# LEDARRAY.net
KiCad netlist of a schematic drawn in EAGLE
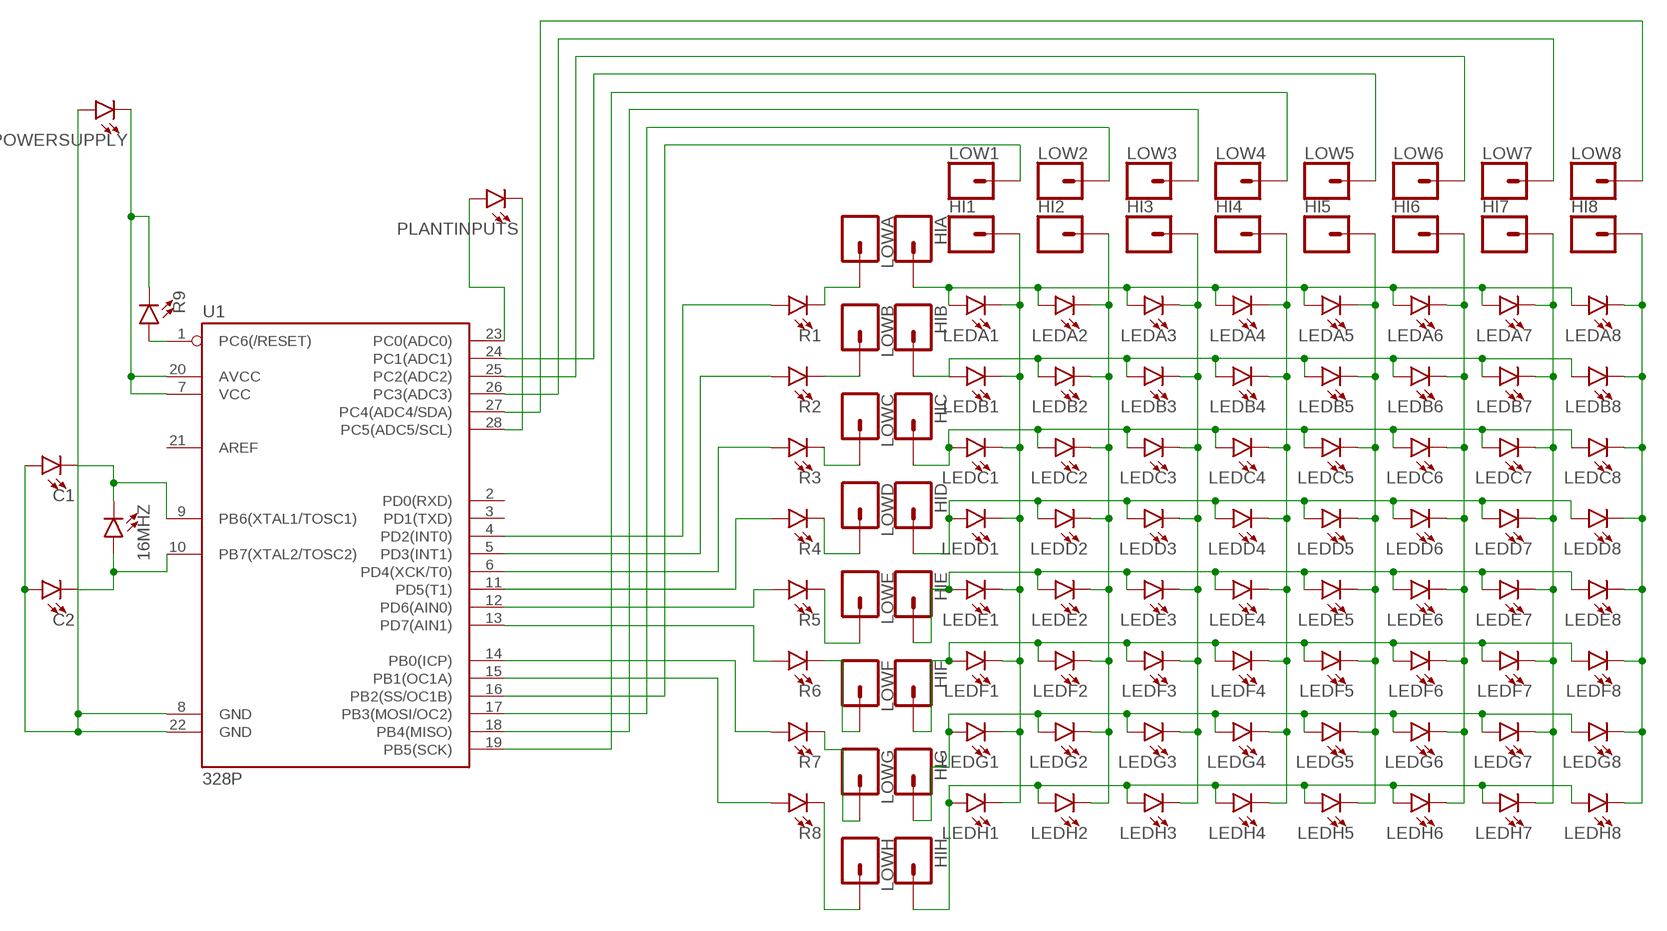
[diagram p0: schematic, sheet 1]

(export (version "E")
  (design (tool "Eeschema 10.0.6"))
  (components
    (comp (ref "16MHZ")
      (value "LED3MM")
      (footprint "eagle-import:LED_3MM")
      (libsource (lib "eagle-import") (part "LED3MM"))
    )
    (comp (ref "C1")
      (value "LED3MM")
      (footprint "eagle-import:LED_3MM")
      (libsource (lib "eagle-import") (part "LED3MM"))
    )
    (comp (ref "C2")
      (value "LED3MM")
      (footprint "eagle-import:LED_3MM")
      (libsource (lib "eagle-import") (part "LED3MM"))
    )
    (comp (ref "HI1")
      (value "CONN_01PTH_NO_SILK_KIT")
      (footprint "eagle-import:1X01NS_KIT")
      (libsource (lib "eagle-import") (part "CONN_01PTH_NO_SILK_KIT"))
    )
    (comp (ref "HI2")
      (value "CONN_01PTH_NO_SILK_KIT")
      (footprint "eagle-import:1X01NS_KIT")
      (libsource (lib "eagle-import") (part "CONN_01PTH_NO_SILK_KIT"))
    )
    (comp (ref "HI3")
      (value "CONN_01PTH_NO_SILK_KIT")
      (footprint "eagle-import:1X01NS_KIT")
      (libsource (lib "eagle-import") (part "CONN_01PTH_NO_SILK_KIT"))
    )
    (comp (ref "HI4")
      (value "CONN_01PTH_NO_SILK_KIT")
      (footprint "eagle-import:1X01NS_KIT")
      (libsource (lib "eagle-import") (part "CONN_01PTH_NO_SILK_KIT"))
    )
    (comp (ref "HI5")
      (value "CONN_01PTH_NO_SILK_KIT")
      (footprint "eagle-import:1X01NS_KIT")
      (libsource (lib "eagle-import") (part "CONN_01PTH_NO_SILK_KIT"))
    )
    (comp (ref "HI6")
      (value "CONN_01PTH_NO_SILK_KIT")
      (footprint "eagle-import:1X01NS_KIT")
      (libsource (lib "eagle-import") (part "CONN_01PTH_NO_SILK_KIT"))
    )
    (comp (ref "HI7")
      (value "CONN_01PTH_NO_SILK_KIT")
      (footprint "eagle-import:1X01NS_KIT")
      (libsource (lib "eagle-import") (part "CONN_01PTH_NO_SILK_KIT"))
    )
    (comp (ref "HI8")
      (value "CONN_01PTH_NO_SILK_KIT")
      (footprint "eagle-import:1X01NS_KIT")
      (libsource (lib "eagle-import") (part "CONN_01PTH_NO_SILK_KIT"))
    )
    (comp (ref "HIA")
      (value "CONN_01PTH_NO_SILK_KIT")
      (footprint "eagle-import:1X01NS_KIT")
      (libsource (lib "eagle-import") (part "CONN_01PTH_NO_SILK_KIT"))
    )
    (comp (ref "HIB")
      (value "CONN_01PTH_NO_SILK_KIT")
      (footprint "eagle-import:1X01NS_KIT")
      (libsource (lib "eagle-import") (part "CONN_01PTH_NO_SILK_KIT"))
    )
    (comp (ref "HIC")
      (value "CONN_01PTH_NO_SILK_KIT")
      (footprint "eagle-import:1X01NS_KIT")
      (libsource (lib "eagle-import") (part "CONN_01PTH_NO_SILK_KIT"))
    )
    (comp (ref "HID")
      (value "CONN_01PTH_NO_SILK_KIT")
      (footprint "eagle-import:1X01NS_KIT")
      (libsource (lib "eagle-import") (part "CONN_01PTH_NO_SILK_KIT"))
    )
    (comp (ref "HIE")
      (value "CONN_01PTH_NO_SILK_KIT")
      (footprint "eagle-import:1X01NS_KIT")
      (libsource (lib "eagle-import") (part "CONN_01PTH_NO_SILK_KIT"))
    )
    (comp (ref "HIF")
      (value "CONN_01PTH_NO_SILK_KIT")
      (footprint "eagle-import:1X01NS_KIT")
      (libsource (lib "eagle-import") (part "CONN_01PTH_NO_SILK_KIT"))
    )
    (comp (ref "HIG")
      (value "CONN_01PTH_NO_SILK_KIT")
      (footprint "eagle-import:1X01NS_KIT")
      (libsource (lib "eagle-import") (part "CONN_01PTH_NO_SILK_KIT"))
    )
    (comp (ref "HIH")
      (value "CONN_01PTH_NO_SILK_KIT")
      (footprint "eagle-import:1X01NS_KIT")
      (libsource (lib "eagle-import") (part "CONN_01PTH_NO_SILK_KIT"))
    )
    (comp (ref "LEDA1")
      (value "LED3MM")
      (footprint "eagle-import:LED_3MM")
      (libsource (lib "eagle-import") (part "LED3MM"))
    )
    (comp (ref "LEDA2")
      (value "LED3MM")
      (footprint "eagle-import:LED_3MM")
      (libsource (lib "eagle-import") (part "LED3MM"))
    )
    (comp (ref "LEDA3")
      (value "LED3MM")
      (footprint "eagle-import:LED_3MM")
      (libsource (lib "eagle-import") (part "LED3MM"))
    )
    (comp (ref "LEDA4")
      (value "LED3MM")
      (footprint "eagle-import:LED_3MM")
      (libsource (lib "eagle-import") (part "LED3MM"))
    )
    (comp (ref "LEDA5")
      (value "LED3MM")
      (footprint "eagle-import:LED_3MM")
      (libsource (lib "eagle-import") (part "LED3MM"))
    )
    (comp (ref "LEDA6")
      (value "LED3MM")
      (footprint "eagle-import:LED_3MM")
      (libsource (lib "eagle-import") (part "LED3MM"))
    )
    (comp (ref "LEDA7")
      (value "LED3MM")
      (footprint "eagle-import:LED_3MM")
      (libsource (lib "eagle-import") (part "LED3MM"))
    )
    (comp (ref "LEDA8")
      (value "LED3MM")
      (footprint "eagle-import:LED_3MM")
      (libsource (lib "eagle-import") (part "LED3MM"))
    )
    (comp (ref "LEDB1")
      (value "LED3MM")
      (footprint "eagle-import:LED_3MM")
      (libsource (lib "eagle-import") (part "LED3MM"))
    )
    (comp (ref "LEDB2")
      (value "LED3MM")
      (footprint "eagle-import:LED_3MM")
      (libsource (lib "eagle-import") (part "LED3MM"))
    )
    (comp (ref "LEDB3")
      (value "LED3MM")
      (footprint "eagle-import:LED_3MM")
      (libsource (lib "eagle-import") (part "LED3MM"))
    )
    (comp (ref "LEDB4")
      (value "LED3MM")
      (footprint "eagle-import:LED_3MM")
      (libsource (lib "eagle-import") (part "LED3MM"))
    )
    (comp (ref "LEDB5")
      (value "LED3MM")
      (footprint "eagle-import:LED_3MM")
      (libsource (lib "eagle-import") (part "LED3MM"))
    )
    (comp (ref "LEDB6")
      (value "LED3MM")
      (footprint "eagle-import:LED_3MM")
      (libsource (lib "eagle-import") (part "LED3MM"))
    )
    (comp (ref "LEDB7")
      (value "LED3MM")
      (footprint "eagle-import:LED_3MM")
      (libsource (lib "eagle-import") (part "LED3MM"))
    )
    (comp (ref "LEDB8")
      (value "LED3MM")
      (footprint "eagle-import:LED_3MM")
      (libsource (lib "eagle-import") (part "LED3MM"))
    )
    (comp (ref "LEDC1")
      (value "LED3MM")
      (footprint "eagle-import:LED_3MM")
      (libsource (lib "eagle-import") (part "LED3MM"))
    )
    (comp (ref "LEDC2")
      (value "LED3MM")
      (footprint "eagle-import:LED_3MM")
      (libsource (lib "eagle-import") (part "LED3MM"))
    )
    (comp (ref "LEDC3")
      (value "LED3MM")
      (footprint "eagle-import:LED_3MM")
      (libsource (lib "eagle-import") (part "LED3MM"))
    )
    (comp (ref "LEDC4")
      (value "LED3MM")
      (footprint "eagle-import:LED_3MM")
      (libsource (lib "eagle-import") (part "LED3MM"))
    )
    (comp (ref "LEDC5")
      (value "LED3MM")
      (footprint "eagle-import:LED_3MM")
      (libsource (lib "eagle-import") (part "LED3MM"))
    )
    (comp (ref "LEDC6")
      (value "LED3MM")
      (footprint "eagle-import:LED_3MM")
      (libsource (lib "eagle-import") (part "LED3MM"))
    )
    (comp (ref "LEDC7")
      (value "LED3MM")
      (footprint "eagle-import:LED_3MM")
      (libsource (lib "eagle-import") (part "LED3MM"))
    )
    (comp (ref "LEDC8")
      (value "LED3MM")
      (footprint "eagle-import:LED_3MM")
      (libsource (lib "eagle-import") (part "LED3MM"))
    )
    (comp (ref "LEDD1")
      (value "LED3MM")
      (footprint "eagle-import:LED_3MM")
      (libsource (lib "eagle-import") (part "LED3MM"))
    )
    (comp (ref "LEDD2")
      (value "LED3MM")
      (footprint "eagle-import:LED_3MM")
      (libsource (lib "eagle-import") (part "LED3MM"))
    )
    (comp (ref "LEDD3")
      (value "LED3MM")
      (footprint "eagle-import:LED_3MM")
      (libsource (lib "eagle-import") (part "LED3MM"))
    )
    (comp (ref "LEDD4")
      (value "LED3MM")
      (footprint "eagle-import:LED_3MM")
      (libsource (lib "eagle-import") (part "LED3MM"))
    )
    (comp (ref "LEDD5")
      (value "LED3MM")
      (footprint "eagle-import:LED_3MM")
      (libsource (lib "eagle-import") (part "LED3MM"))
    )
    (comp (ref "LEDD6")
      (value "LED3MM")
      (footprint "eagle-import:LED_3MM")
      (libsource (lib "eagle-import") (part "LED3MM"))
    )
    (comp (ref "LEDD7")
      (value "LED3MM")
      (footprint "eagle-import:LED_3MM")
      (libsource (lib "eagle-import") (part "LED3MM"))
    )
    (comp (ref "LEDD8")
      (value "LED3MM")
      (footprint "eagle-import:LED_3MM")
      (libsource (lib "eagle-import") (part "LED3MM"))
    )
    (comp (ref "LEDE1")
      (value "LED3MM")
      (footprint "eagle-import:LED_3MM")
      (libsource (lib "eagle-import") (part "LED3MM"))
    )
    (comp (ref "LEDE2")
      (value "LED3MM")
      (footprint "eagle-import:LED_3MM")
      (libsource (lib "eagle-import") (part "LED3MM"))
    )
    (comp (ref "LEDE3")
      (value "LED3MM")
      (footprint "eagle-import:LED_3MM")
      (libsource (lib "eagle-import") (part "LED3MM"))
    )
    (comp (ref "LEDE4")
      (value "LED3MM")
      (footprint "eagle-import:LED_3MM")
      (libsource (lib "eagle-import") (part "LED3MM"))
    )
    (comp (ref "LEDE5")
      (value "LED3MM")
      (footprint "eagle-import:LED_3MM")
      (libsource (lib "eagle-import") (part "LED3MM"))
    )
    (comp (ref "LEDE6")
      (value "LED3MM")
      (footprint "eagle-import:LED_3MM")
      (libsource (lib "eagle-import") (part "LED3MM"))
    )
    (comp (ref "LEDE7")
      (value "LED3MM")
      (footprint "eagle-import:LED_3MM")
      (libsource (lib "eagle-import") (part "LED3MM"))
    )
    (comp (ref "LEDE8")
      (value "LED3MM")
      (footprint "eagle-import:LED_3MM")
      (libsource (lib "eagle-import") (part "LED3MM"))
    )
    (comp (ref "LEDF1")
      (value "LED3MM")
      (footprint "eagle-import:LED_3MM")
      (libsource (lib "eagle-import") (part "LED3MM"))
    )
    (comp (ref "LEDF2")
      (value "LED3MM")
      (footprint "eagle-import:LED_3MM")
      (libsource (lib "eagle-import") (part "LED3MM"))
    )
    (comp (ref "LEDF3")
      (value "LED3MM")
      (footprint "eagle-import:LED_3MM")
      (libsource (lib "eagle-import") (part "LED3MM"))
    )
    (comp (ref "LEDF4")
      (value "LED3MM")
      (footprint "eagle-import:LED_3MM")
      (libsource (lib "eagle-import") (part "LED3MM"))
    )
    (comp (ref "LEDF5")
      (value "LED3MM")
      (footprint "eagle-import:LED_3MM")
      (libsource (lib "eagle-import") (part "LED3MM"))
    )
    (comp (ref "LEDF6")
      (value "LED3MM")
      (footprint "eagle-import:LED_3MM")
      (libsource (lib "eagle-import") (part "LED3MM"))
    )
    (comp (ref "LEDF7")
      (value "LED3MM")
      (footprint "eagle-import:LED_3MM")
      (libsource (lib "eagle-import") (part "LED3MM"))
    )
    (comp (ref "LEDF8")
      (value "LED3MM")
      (footprint "eagle-import:LED_3MM")
      (libsource (lib "eagle-import") (part "LED3MM"))
    )
    (comp (ref "LEDG1")
      (value "LED3MM")
      (footprint "eagle-import:LED_3MM")
      (libsource (lib "eagle-import") (part "LED3MM"))
    )
    (comp (ref "LEDG2")
      (value "LED3MM")
      (footprint "eagle-import:LED_3MM")
      (libsource (lib "eagle-import") (part "LED3MM"))
    )
    (comp (ref "LEDG3")
      (value "LED3MM")
      (footprint "eagle-import:LED_3MM")
      (libsource (lib "eagle-import") (part "LED3MM"))
    )
    (comp (ref "LEDG4")
      (value "LED3MM")
      (footprint "eagle-import:LED_3MM")
      (libsource (lib "eagle-import") (part "LED3MM"))
    )
    (comp (ref "LEDG5")
      (value "LED3MM")
      (footprint "eagle-import:LED_3MM")
      (libsource (lib "eagle-import") (part "LED3MM"))
    )
    (comp (ref "LEDG6")
      (value "LED3MM")
      (footprint "eagle-import:LED_3MM")
      (libsource (lib "eagle-import") (part "LED3MM"))
    )
    (comp (ref "LEDG7")
      (value "LED3MM")
      (footprint "eagle-import:LED_3MM")
      (libsource (lib "eagle-import") (part "LED3MM"))
    )
    (comp (ref "LEDG8")
      (value "LED3MM")
      (footprint "eagle-import:LED_3MM")
      (libsource (lib "eagle-import") (part "LED3MM"))
    )
    (comp (ref "LEDH1")
      (value "LED3MM")
      (footprint "eagle-import:LED_3MM")
      (libsource (lib "eagle-import") (part "LED3MM"))
    )
    (comp (ref "LEDH2")
      (value "LED3MM")
      (footprint "eagle-import:LED_3MM")
      (libsource (lib "eagle-import") (part "LED3MM"))
    )
    (comp (ref "LEDH3")
      (value "LED3MM")
      (footprint "eagle-import:LED_3MM")
      (libsource (lib "eagle-import") (part "LED3MM"))
    )
    (comp (ref "LEDH4")
      (value "LED3MM")
      (footprint "eagle-import:LED_3MM")
      (libsource (lib "eagle-import") (part "LED3MM"))
    )
    (comp (ref "LEDH5")
      (value "LED3MM")
      (footprint "eagle-import:LED_3MM")
      (libsource (lib "eagle-import") (part "LED3MM"))
    )
    (comp (ref "LEDH6")
      (value "LED3MM")
      (footprint "eagle-import:LED_3MM")
      (libsource (lib "eagle-import") (part "LED3MM"))
    )
    (comp (ref "LEDH7")
      (value "LED3MM")
      (footprint "eagle-import:LED_3MM")
      (libsource (lib "eagle-import") (part "LED3MM"))
    )
    (comp (ref "LEDH8")
      (value "LED3MM")
      (footprint "eagle-import:LED_3MM")
      (libsource (lib "eagle-import") (part "LED3MM"))
    )
    (comp (ref "LOW1")
      (value "CONN_01PTH_NO_SILK_KIT")
      (footprint "eagle-import:1X01NS_KIT")
      (libsource (lib "eagle-import") (part "CONN_01PTH_NO_SILK_KIT"))
    )
    (comp (ref "LOW2")
      (value "CONN_01PTH_NO_SILK_KIT")
      (footprint "eagle-import:1X01NS_KIT")
      (libsource (lib "eagle-import") (part "CONN_01PTH_NO_SILK_KIT"))
    )
    (comp (ref "LOW3")
      (value "CONN_01PTH_NO_SILK_KIT")
      (footprint "eagle-import:1X01NS_KIT")
      (libsource (lib "eagle-import") (part "CONN_01PTH_NO_SILK_KIT"))
    )
    (comp (ref "LOW4")
      (value "CONN_01PTH_NO_SILK_KIT")
      (footprint "eagle-import:1X01NS_KIT")
      (libsource (lib "eagle-import") (part "CONN_01PTH_NO_SILK_KIT"))
    )
    (comp (ref "LOW5")
      (value "CONN_01PTH_NO_SILK_KIT")
      (footprint "eagle-import:1X01NS_KIT")
      (libsource (lib "eagle-import") (part "CONN_01PTH_NO_SILK_KIT"))
    )
    (comp (ref "LOW6")
      (value "CONN_01PTH_NO_SILK_KIT")
      (footprint "eagle-import:1X01NS_KIT")
      (libsource (lib "eagle-import") (part "CONN_01PTH_NO_SILK_KIT"))
    )
    (comp (ref "LOW7")
      (value "CONN_01PTH_NO_SILK_KIT")
      (footprint "eagle-import:1X01NS_KIT")
      (libsource (lib "eagle-import") (part "CONN_01PTH_NO_SILK_KIT"))
    )
    (comp (ref "LOW8")
      (value "CONN_01PTH_NO_SILK_KIT")
      (footprint "eagle-import:1X01NS_KIT")
      (libsource (lib "eagle-import") (part "CONN_01PTH_NO_SILK_KIT"))
    )
    (comp (ref "LOWA")
      (value "CONN_01PTH_NO_SILK_KIT")
      (footprint "eagle-import:1X01NS_KIT")
      (libsource (lib "eagle-import") (part "CONN_01PTH_NO_SILK_KIT"))
    )
    (comp (ref "LOWB")
      (value "CONN_01PTH_NO_SILK_KIT")
      (footprint "eagle-import:1X01NS_KIT")
      (libsource (lib "eagle-import") (part "CONN_01PTH_NO_SILK_KIT"))
    )
    (comp (ref "LOWC")
      (value "CONN_01PTH_NO_SILK_KIT")
      (footprint "eagle-import:1X01NS_KIT")
      (libsource (lib "eagle-import") (part "CONN_01PTH_NO_SILK_KIT"))
    )
    (comp (ref "LOWD")
      (value "CONN_01PTH_NO_SILK_KIT")
      (footprint "eagle-import:1X01NS_KIT")
      (libsource (lib "eagle-import") (part "CONN_01PTH_NO_SILK_KIT"))
    )
    (comp (ref "LOWE")
      (value "CONN_01PTH_NO_SILK_KIT")
      (footprint "eagle-import:1X01NS_KIT")
      (libsource (lib "eagle-import") (part "CONN_01PTH_NO_SILK_KIT"))
    )
    (comp (ref "LOWF")
      (value "CONN_01PTH_NO_SILK_KIT")
      (footprint "eagle-import:1X01NS_KIT")
      (libsource (lib "eagle-import") (part "CONN_01PTH_NO_SILK_KIT"))
    )
    (comp (ref "LOWG")
      (value "CONN_01PTH_NO_SILK_KIT")
      (footprint "eagle-import:1X01NS_KIT")
      (libsource (lib "eagle-import") (part "CONN_01PTH_NO_SILK_KIT"))
    )
    (comp (ref "LOWH")
      (value "CONN_01PTH_NO_SILK_KIT")
      (footprint "eagle-import:1X01NS_KIT")
      (libsource (lib "eagle-import") (part "CONN_01PTH_NO_SILK_KIT"))
    )
    (comp (ref "PLANTINPUTS")
      (value "LED3MM")
      (footprint "eagle-import:LED_3MM")
      (libsource (lib "eagle-import") (part "LED3MM"))
    )
    (comp (ref "POWERSUPPLY")
      (value "LED3MM")
      (footprint "eagle-import:LED_3MM")
      (libsource (lib "eagle-import") (part "LED3MM"))
    )
    (comp (ref "R1")
      (value "LED3MM")
      (footprint "eagle-import:LED_3MM")
      (libsource (lib "eagle-import") (part "LED3MM"))
    )
    (comp (ref "R2")
      (value "LED3MM")
      (footprint "eagle-import:LED_3MM")
      (libsource (lib "eagle-import") (part "LED3MM"))
    )
    (comp (ref "R3")
      (value "LED3MM")
      (footprint "eagle-import:LED_3MM")
      (libsource (lib "eagle-import") (part "LED3MM"))
    )
    (comp (ref "R4")
      (value "LED3MM")
      (footprint "eagle-import:LED_3MM")
      (libsource (lib "eagle-import") (part "LED3MM"))
    )
    (comp (ref "R5")
      (value "LED3MM")
      (footprint "eagle-import:LED_3MM")
      (libsource (lib "eagle-import") (part "LED3MM"))
    )
    (comp (ref "R6")
      (value "LED3MM")
      (footprint "eagle-import:LED_3MM")
      (libsource (lib "eagle-import") (part "LED3MM"))
    )
    (comp (ref "R7")
      (value "LED3MM")
      (footprint "eagle-import:LED_3MM")
      (libsource (lib "eagle-import") (part "LED3MM"))
    )
    (comp (ref "R8")
      (value "LED3MM")
      (footprint "eagle-import:LED_3MM")
      (libsource (lib "eagle-import") (part "LED3MM"))
    )
    (comp (ref "R9")
      (value "LED3MM")
      (footprint "eagle-import:LED_3MM")
      (libsource (lib "eagle-import") (part "LED3MM"))
    )
    (comp (ref "U1")
      (value "328P")
      (footprint "eagle-import:DIP28")
      (libsource (lib "eagle-import") (part "ATMEGA328P_PDIP"))
    )
  )
  (nets
    (net (code "1") (name "Net-(16MHZ-C)") (class "Default")
      (node (ref "16MHZ") (pin "K") (pinfunction "C_K") (pintype "passive"))
      (node (ref "C1") (pin "K") (pinfunction "C_K") (pintype "passive"))
      (node (ref "U1") (pin "9") (pinfunction "PB6(XTAL1/TOSC1)_9") (pintype "bidirectional"))
    )
    (net (code "2") (name "Net-(C1-PadA)") (class "Default")
      (node (ref "C1") (pin "A") (pinfunction "A_A") (pintype "passive"))
      (node (ref "C2") (pin "A") (pinfunction "A_A") (pintype "passive"))
      (node (ref "POWERSUPPLY") (pin "A") (pinfunction "A_A") (pintype "passive"))
      (node (ref "U1") (pin "22") (pinfunction "GND_22") (pintype "bidirectional"))
      (node (ref "U1") (pin "8") (pinfunction "GND_8") (pintype "bidirectional"))
    )
    (net (code "3") (name "Net-(C2-C)") (class "Default")
      (node (ref "16MHZ") (pin "A") (pinfunction "A_A") (pintype "passive"))
      (node (ref "C2") (pin "K") (pinfunction "C_K") (pintype "passive"))
      (node (ref "U1") (pin "10") (pinfunction "PB7(XTAL2/TOSC2)_10") (pintype "bidirectional"))
    )
    (net (code "4") (name "Net-(HIA-Pad1)") (class "Default")
      (node (ref "HIA") (pin "1") (pinfunction "1_1") (pintype "passive"))
      (node (ref "LEDA1") (pin "A") (pinfunction "A_A") (pintype "passive"))
      (node (ref "LEDA2") (pin "A") (pinfunction "A_A") (pintype "passive"))
      (node (ref "LEDA3") (pin "A") (pinfunction "A_A") (pintype "passive"))
      (node (ref "LEDA4") (pin "A") (pinfunction "A_A") (pintype "passive"))
      (node (ref "LEDA5") (pin "A") (pinfunction "A_A") (pintype "passive"))
      (node (ref "LEDA6") (pin "A") (pinfunction "A_A") (pintype "passive"))
      (node (ref "LEDA7") (pin "A") (pinfunction "A_A") (pintype "passive"))
      (node (ref "LEDA8") (pin "A") (pinfunction "A_A") (pintype "passive"))
    )
    (net (code "5") (name "Net-(HIB-Pad1)") (class "Default")
      (node (ref "HIB") (pin "1") (pinfunction "1_1") (pintype "passive"))
      (node (ref "LEDB1") (pin "A") (pinfunction "A_A") (pintype "passive"))
      (node (ref "LEDB2") (pin "A") (pinfunction "A_A") (pintype "passive"))
      (node (ref "LEDB3") (pin "A") (pinfunction "A_A") (pintype "passive"))
      (node (ref "LEDB4") (pin "A") (pinfunction "A_A") (pintype "passive"))
      (node (ref "LEDB5") (pin "A") (pinfunction "A_A") (pintype "passive"))
      (node (ref "LEDB6") (pin "A") (pinfunction "A_A") (pintype "passive"))
      (node (ref "LEDB7") (pin "A") (pinfunction "A_A") (pintype "passive"))
      (node (ref "LEDB8") (pin "A") (pinfunction "A_A") (pintype "passive"))
    )
    (net (code "6") (name "Net-(HIC-Pad1)") (class "Default")
      (node (ref "HIC") (pin "1") (pinfunction "1_1") (pintype "passive"))
      (node (ref "LEDC1") (pin "A") (pinfunction "A_A") (pintype "passive"))
      (node (ref "LEDC2") (pin "A") (pinfunction "A_A") (pintype "passive"))
      (node (ref "LEDC3") (pin "A") (pinfunction "A_A") (pintype "passive"))
      (node (ref "LEDC4") (pin "A") (pinfunction "A_A") (pintype "passive"))
      (node (ref "LEDC5") (pin "A") (pinfunction "A_A") (pintype "passive"))
      (node (ref "LEDC6") (pin "A") (pinfunction "A_A") (pintype "passive"))
      (node (ref "LEDC7") (pin "A") (pinfunction "A_A") (pintype "passive"))
      (node (ref "LEDC8") (pin "A") (pinfunction "A_A") (pintype "passive"))
    )
    (net (code "7") (name "Net-(HID-Pad1)") (class "Default")
      (node (ref "HID") (pin "1") (pinfunction "1_1") (pintype "passive"))
      (node (ref "LEDD1") (pin "A") (pinfunction "A_A") (pintype "passive"))
      (node (ref "LEDD2") (pin "A") (pinfunction "A_A") (pintype "passive"))
      (node (ref "LEDD3") (pin "A") (pinfunction "A_A") (pintype "passive"))
      (node (ref "LEDD4") (pin "A") (pinfunction "A_A") (pintype "passive"))
      (node (ref "LEDD5") (pin "A") (pinfunction "A_A") (pintype "passive"))
      (node (ref "LEDD6") (pin "A") (pinfunction "A_A") (pintype "passive"))
      (node (ref "LEDD7") (pin "A") (pinfunction "A_A") (pintype "passive"))
      (node (ref "LEDD8") (pin "A") (pinfunction "A_A") (pintype "passive"))
    )
    (net (code "8") (name "Net-(HIE-Pad1)") (class "Default")
      (node (ref "HIE") (pin "1") (pinfunction "1_1") (pintype "passive"))
      (node (ref "LEDE1") (pin "A") (pinfunction "A_A") (pintype "passive"))
      (node (ref "LEDE2") (pin "A") (pinfunction "A_A") (pintype "passive"))
      (node (ref "LEDE3") (pin "A") (pinfunction "A_A") (pintype "passive"))
      (node (ref "LEDE4") (pin "A") (pinfunction "A_A") (pintype "passive"))
      (node (ref "LEDE5") (pin "A") (pinfunction "A_A") (pintype "passive"))
      (node (ref "LEDE6") (pin "A") (pinfunction "A_A") (pintype "passive"))
      (node (ref "LEDE7") (pin "A") (pinfunction "A_A") (pintype "passive"))
      (node (ref "LEDE8") (pin "A") (pinfunction "A_A") (pintype "passive"))
    )
    (net (code "9") (name "Net-(HIF-Pad1)") (class "Default")
      (node (ref "HIF") (pin "1") (pinfunction "1_1") (pintype "passive"))
      (node (ref "LEDF1") (pin "A") (pinfunction "A_A") (pintype "passive"))
      (node (ref "LEDF2") (pin "A") (pinfunction "A_A") (pintype "passive"))
      (node (ref "LEDF3") (pin "A") (pinfunction "A_A") (pintype "passive"))
      (node (ref "LEDF4") (pin "A") (pinfunction "A_A") (pintype "passive"))
      (node (ref "LEDF5") (pin "A") (pinfunction "A_A") (pintype "passive"))
      (node (ref "LEDF6") (pin "A") (pinfunction "A_A") (pintype "passive"))
      (node (ref "LEDF7") (pin "A") (pinfunction "A_A") (pintype "passive"))
      (node (ref "LEDF8") (pin "A") (pinfunction "A_A") (pintype "passive"))
    )
    (net (code "10") (name "Net-(HIG-Pad1)") (class "Default")
      (node (ref "HIG") (pin "1") (pinfunction "1_1") (pintype "passive"))
      (node (ref "LEDG1") (pin "A") (pinfunction "A_A") (pintype "passive"))
      (node (ref "LEDG2") (pin "A") (pinfunction "A_A") (pintype "passive"))
      (node (ref "LEDG3") (pin "A") (pinfunction "A_A") (pintype "passive"))
      (node (ref "LEDG4") (pin "A") (pinfunction "A_A") (pintype "passive"))
      (node (ref "LEDG5") (pin "A") (pinfunction "A_A") (pintype "passive"))
      (node (ref "LEDG6") (pin "A") (pinfunction "A_A") (pintype "passive"))
      (node (ref "LEDG7") (pin "A") (pinfunction "A_A") (pintype "passive"))
      (node (ref "LEDG8") (pin "A") (pinfunction "A_A") (pintype "passive"))
    )
    (net (code "11") (name "Net-(HIH-Pad1)") (class "Default")
      (node (ref "HIH") (pin "1") (pinfunction "1_1") (pintype "passive"))
      (node (ref "LEDH1") (pin "A") (pinfunction "A_A") (pintype "passive"))
      (node (ref "LEDH2") (pin "A") (pinfunction "A_A") (pintype "passive"))
      (node (ref "LEDH3") (pin "A") (pinfunction "A_A") (pintype "passive"))
      (node (ref "LEDH4") (pin "A") (pinfunction "A_A") (pintype "passive"))
      (node (ref "LEDH5") (pin "A") (pinfunction "A_A") (pintype "passive"))
      (node (ref "LEDH6") (pin "A") (pinfunction "A_A") (pintype "passive"))
      (node (ref "LEDH7") (pin "A") (pinfunction "A_A") (pintype "passive"))
      (node (ref "LEDH8") (pin "A") (pinfunction "A_A") (pintype "passive"))
    )
    (net (code "12") (name "Net-(LEDA1-C)") (class "Default")
      (node (ref "HI1") (pin "1") (pinfunction "1_1") (pintype "passive"))
      (node (ref "LEDA1") (pin "K") (pinfunction "C_K") (pintype "passive"))
      (node (ref "LEDB1") (pin "K") (pinfunction "C_K") (pintype "passive"))
      (node (ref "LEDC1") (pin "K") (pinfunction "C_K") (pintype "passive"))
      (node (ref "LEDD1") (pin "K") (pinfunction "C_K") (pintype "passive"))
      (node (ref "LEDE1") (pin "K") (pinfunction "C_K") (pintype "passive"))
      (node (ref "LEDF1") (pin "K") (pinfunction "C_K") (pintype "passive"))
      (node (ref "LEDG1") (pin "K") (pinfunction "C_K") (pintype "passive"))
      (node (ref "LEDH1") (pin "K") (pinfunction "C_K") (pintype "passive"))
    )
    (net (code "13") (name "Net-(LEDA2-C)") (class "Default")
      (node (ref "HI2") (pin "1") (pinfunction "1_1") (pintype "passive"))
      (node (ref "LEDA2") (pin "K") (pinfunction "C_K") (pintype "passive"))
      (node (ref "LEDB2") (pin "K") (pinfunction "C_K") (pintype "passive"))
      (node (ref "LEDC2") (pin "K") (pinfunction "C_K") (pintype "passive"))
      (node (ref "LEDD2") (pin "K") (pinfunction "C_K") (pintype "passive"))
      (node (ref "LEDE2") (pin "K") (pinfunction "C_K") (pintype "passive"))
      (node (ref "LEDF2") (pin "K") (pinfunction "C_K") (pintype "passive"))
      (node (ref "LEDG2") (pin "K") (pinfunction "C_K") (pintype "passive"))
      (node (ref "LEDH2") (pin "K") (pinfunction "C_K") (pintype "passive"))
    )
    (net (code "14") (name "Net-(LEDA3-C)") (class "Default")
      (node (ref "HI3") (pin "1") (pinfunction "1_1") (pintype "passive"))
      (node (ref "LEDA3") (pin "K") (pinfunction "C_K") (pintype "passive"))
      (node (ref "LEDB3") (pin "K") (pinfunction "C_K") (pintype "passive"))
      (node (ref "LEDC3") (pin "K") (pinfunction "C_K") (pintype "passive"))
      (node (ref "LEDD3") (pin "K") (pinfunction "C_K") (pintype "passive"))
      (node (ref "LEDE3") (pin "K") (pinfunction "C_K") (pintype "passive"))
      (node (ref "LEDF3") (pin "K") (pinfunction "C_K") (pintype "passive"))
      (node (ref "LEDG3") (pin "K") (pinfunction "C_K") (pintype "passive"))
      (node (ref "LEDH3") (pin "K") (pinfunction "C_K") (pintype "passive"))
    )
    (net (code "15") (name "Net-(LEDA4-C)") (class "Default")
      (node (ref "HI4") (pin "1") (pinfunction "1_1") (pintype "passive"))
      (node (ref "LEDA4") (pin "K") (pinfunction "C_K") (pintype "passive"))
      (node (ref "LEDB4") (pin "K") (pinfunction "C_K") (pintype "passive"))
      (node (ref "LEDC4") (pin "K") (pinfunction "C_K") (pintype "passive"))
      (node (ref "LEDD4") (pin "K") (pinfunction "C_K") (pintype "passive"))
      (node (ref "LEDE4") (pin "K") (pinfunction "C_K") (pintype "passive"))
      (node (ref "LEDF4") (pin "K") (pinfunction "C_K") (pintype "passive"))
      (node (ref "LEDG4") (pin "K") (pinfunction "C_K") (pintype "passive"))
      (node (ref "LEDH4") (pin "K") (pinfunction "C_K") (pintype "passive"))
    )
    (net (code "16") (name "Net-(LEDA5-C)") (class "Default")
      (node (ref "HI5") (pin "1") (pinfunction "1_1") (pintype "passive"))
      (node (ref "LEDA5") (pin "K") (pinfunction "C_K") (pintype "passive"))
      (node (ref "LEDB5") (pin "K") (pinfunction "C_K") (pintype "passive"))
      (node (ref "LEDC5") (pin "K") (pinfunction "C_K") (pintype "passive"))
      (node (ref "LEDD5") (pin "K") (pinfunction "C_K") (pintype "passive"))
      (node (ref "LEDE5") (pin "K") (pinfunction "C_K") (pintype "passive"))
      (node (ref "LEDF5") (pin "K") (pinfunction "C_K") (pintype "passive"))
      (node (ref "LEDG5") (pin "K") (pinfunction "C_K") (pintype "passive"))
      (node (ref "LEDH5") (pin "K") (pinfunction "C_K") (pintype "passive"))
    )
    (net (code "17") (name "Net-(LEDA6-C)") (class "Default")
      (node (ref "HI6") (pin "1") (pinfunction "1_1") (pintype "passive"))
      (node (ref "LEDA6") (pin "K") (pinfunction "C_K") (pintype "passive"))
      (node (ref "LEDB6") (pin "K") (pinfunction "C_K") (pintype "passive"))
      (node (ref "LEDC6") (pin "K") (pinfunction "C_K") (pintype "passive"))
      (node (ref "LEDD6") (pin "K") (pinfunction "C_K") (pintype "passive"))
      (node (ref "LEDE6") (pin "K") (pinfunction "C_K") (pintype "passive"))
      (node (ref "LEDF6") (pin "K") (pinfunction "C_K") (pintype "passive"))
      (node (ref "LEDG6") (pin "K") (pinfunction "C_K") (pintype "passive"))
      (node (ref "LEDH6") (pin "K") (pinfunction "C_K") (pintype "passive"))
    )
    (net (code "18") (name "Net-(LEDA7-C)") (class "Default")
      (node (ref "HI7") (pin "1") (pinfunction "1_1") (pintype "passive"))
      (node (ref "LEDA7") (pin "K") (pinfunction "C_K") (pintype "passive"))
      (node (ref "LEDB7") (pin "K") (pinfunction "C_K") (pintype "passive"))
      (node (ref "LEDC7") (pin "K") (pinfunction "C_K") (pintype "passive"))
      (node (ref "LEDD7") (pin "K") (pinfunction "C_K") (pintype "passive"))
      (node (ref "LEDE7") (pin "K") (pinfunction "C_K") (pintype "passive"))
      (node (ref "LEDF7") (pin "K") (pinfunction "C_K") (pintype "passive"))
      (node (ref "LEDG7") (pin "K") (pinfunction "C_K") (pintype "passive"))
      (node (ref "LEDH7") (pin "K") (pinfunction "C_K") (pintype "passive"))
    )
    (net (code "19") (name "Net-(LEDA8-C)") (class "Default")
      (node (ref "HI8") (pin "1") (pinfunction "1_1") (pintype "passive"))
      (node (ref "LEDA8") (pin "K") (pinfunction "C_K") (pintype "passive"))
      (node (ref "LEDB8") (pin "K") (pinfunction "C_K") (pintype "passive"))
      (node (ref "LEDC8") (pin "K") (pinfunction "C_K") (pintype "passive"))
      (node (ref "LEDD8") (pin "K") (pinfunction "C_K") (pintype "passive"))
      (node (ref "LEDE8") (pin "K") (pinfunction "C_K") (pintype "passive"))
      (node (ref "LEDF8") (pin "K") (pinfunction "C_K") (pintype "passive"))
      (node (ref "LEDG8") (pin "K") (pinfunction "C_K") (pintype "passive"))
      (node (ref "LEDH8") (pin "K") (pinfunction "C_K") (pintype "passive"))
    )
    (net (code "20") (name "Net-(PLANTINPUTS-C)") (class "Default")
      (node (ref "PLANTINPUTS") (pin "K") (pinfunction "C_K") (pintype "passive"))
      (node (ref "U1") (pin "28") (pinfunction "PC5(ADC5/SCL)_28") (pintype "bidirectional"))
    )
    (net (code "21") (name "Net-(POWERSUPPLY-C)") (class "Default")
      (node (ref "POWERSUPPLY") (pin "K") (pinfunction "C_K") (pintype "passive"))
      (node (ref "R9") (pin "K") (pinfunction "C_K") (pintype "passive"))
      (node (ref "U1") (pin "20") (pinfunction "AVCC_20") (pintype "bidirectional"))
      (node (ref "U1") (pin "7") (pinfunction "VCC_7") (pintype "bidirectional"))
    )
    (net (code "22") (name "Net-(R1-C)") (class "Default")
      (node (ref "LOWA") (pin "1") (pinfunction "1_1") (pintype "passive"))
      (node (ref "R1") (pin "K") (pinfunction "C_K") (pintype "passive"))
    )
    (net (code "23") (name "Net-(R2-C)") (class "Default")
      (node (ref "LOWB") (pin "1") (pinfunction "1_1") (pintype "passive"))
      (node (ref "R2") (pin "K") (pinfunction "C_K") (pintype "passive"))
    )
    (net (code "24") (name "Net-(R3-C)") (class "Default")
      (node (ref "LOWC") (pin "1") (pinfunction "1_1") (pintype "passive"))
      (node (ref "R3") (pin "K") (pinfunction "C_K") (pintype "passive"))
    )
    (net (code "25") (name "Net-(R4-C)") (class "Default")
      (node (ref "LOWD") (pin "1") (pinfunction "1_1") (pintype "passive"))
      (node (ref "R4") (pin "K") (pinfunction "C_K") (pintype "passive"))
    )
    (net (code "26") (name "Net-(R5-C)") (class "Default")
      (node (ref "LOWE") (pin "1") (pinfunction "1_1") (pintype "passive"))
      (node (ref "R5") (pin "K") (pinfunction "C_K") (pintype "passive"))
    )
    (net (code "27") (name "Net-(R6-C)") (class "Default")
      (node (ref "LOWF") (pin "1") (pinfunction "1_1") (pintype "passive"))
      (node (ref "R6") (pin "K") (pinfunction "C_K") (pintype "passive"))
    )
    (net (code "28") (name "Net-(R7-C)") (class "Default")
      (node (ref "LOWG") (pin "1") (pinfunction "1_1") (pintype "passive"))
      (node (ref "R7") (pin "K") (pinfunction "C_K") (pintype "passive"))
    )
    (net (code "29") (name "Net-(R8-C)") (class "Default")
      (node (ref "LOWH") (pin "1") (pinfunction "1_1") (pintype "passive"))
      (node (ref "R8") (pin "K") (pinfunction "C_K") (pintype "passive"))
    )
    (net (code "30") (name "Net-(U1-PB0(ICP))") (class "Default")
      (node (ref "R7") (pin "A") (pinfunction "A_A") (pintype "passive"))
      (node (ref "U1") (pin "14") (pinfunction "PB0(ICP)_14") (pintype "bidirectional"))
    )
    (net (code "31") (name "Net-(U1-PB1(OC1A))") (class "Default")
      (node (ref "R8") (pin "A") (pinfunction "A_A") (pintype "passive"))
      (node (ref "U1") (pin "15") (pinfunction "PB1(OC1A)_15") (pintype "bidirectional"))
    )
    (net (code "32") (name "Net-(U1-PB2(SS{slash}OC1B))") (class "Default")
      (node (ref "LOW1") (pin "1") (pinfunction "1_1") (pintype "passive"))
      (node (ref "U1") (pin "16") (pinfunction "PB2(SS/OC1B)_16") (pintype "bidirectional"))
    )
    (net (code "33") (name "Net-(U1-PB3(MOSI{slash}OC2))") (class "Default")
      (node (ref "LOW2") (pin "1") (pinfunction "1_1") (pintype "passive"))
      (node (ref "U1") (pin "17") (pinfunction "PB3(MOSI/OC2)_17") (pintype "bidirectional"))
    )
    (net (code "34") (name "Net-(U1-PB4(MISO))") (class "Default")
      (node (ref "LOW3") (pin "1") (pinfunction "1_1") (pintype "passive"))
      (node (ref "U1") (pin "18") (pinfunction "PB4(MISO)_18") (pintype "bidirectional"))
    )
    (net (code "35") (name "Net-(U1-PB5(SCK))") (class "Default")
      (node (ref "LOW4") (pin "1") (pinfunction "1_1") (pintype "passive"))
      (node (ref "U1") (pin "19") (pinfunction "PB5(SCK)_19") (pintype "bidirectional"))
    )
    (net (code "36") (name "Net-(U1-PC0(ADC0))") (class "Default")
      (node (ref "PLANTINPUTS") (pin "A") (pinfunction "A_A") (pintype "passive"))
      (node (ref "U1") (pin "23") (pinfunction "PC0(ADC0)_23") (pintype "bidirectional"))
    )
    (net (code "37") (name "Net-(U1-PC1(ADC1))") (class "Default")
      (node (ref "LOW5") (pin "1") (pinfunction "1_1") (pintype "passive"))
      (node (ref "U1") (pin "24") (pinfunction "PC1(ADC1)_24") (pintype "bidirectional"))
    )
    (net (code "38") (name "Net-(U1-PC2(ADC2))") (class "Default")
      (node (ref "LOW6") (pin "1") (pinfunction "1_1") (pintype "passive"))
      (node (ref "U1") (pin "25") (pinfunction "PC2(ADC2)_25") (pintype "bidirectional"))
    )
    (net (code "39") (name "Net-(U1-PC3(ADC3))") (class "Default")
      (node (ref "LOW7") (pin "1") (pinfunction "1_1") (pintype "passive"))
      (node (ref "U1") (pin "26") (pinfunction "PC3(ADC3)_26") (pintype "bidirectional"))
    )
    (net (code "40") (name "Net-(U1-PC4(ADC4{slash}SDA))") (class "Default")
      (node (ref "LOW8") (pin "1") (pinfunction "1_1") (pintype "passive"))
      (node (ref "U1") (pin "27") (pinfunction "PC4(ADC4/SDA)_27") (pintype "bidirectional"))
    )
    (net (code "41") (name "Net-(U1-PC6({slash}RESET))") (class "Default")
      (node (ref "R9") (pin "A") (pinfunction "A_A") (pintype "passive"))
      (node (ref "U1") (pin "1") (pinfunction "PC6(/RESET)_1") (pintype "bidirectional"))
    )
    (net (code "42") (name "Net-(U1-PD2(INT0))") (class "Default")
      (node (ref "R1") (pin "A") (pinfunction "A_A") (pintype "passive"))
      (node (ref "U1") (pin "4") (pinfunction "PD2(INT0)_4") (pintype "bidirectional"))
    )
    (net (code "43") (name "Net-(U1-PD3(INT1))") (class "Default")
      (node (ref "R2") (pin "A") (pinfunction "A_A") (pintype "passive"))
      (node (ref "U1") (pin "5") (pinfunction "PD3(INT1)_5") (pintype "bidirectional"))
    )
    (net (code "44") (name "Net-(U1-PD4(XCK{slash}T0))") (class "Default")
      (node (ref "R3") (pin "A") (pinfunction "A_A") (pintype "passive"))
      (node (ref "U1") (pin "6") (pinfunction "PD4(XCK/T0)_6") (pintype "bidirectional"))
    )
    (net (code "45") (name "Net-(U1-PD5(T1))") (class "Default")
      (node (ref "R4") (pin "A") (pinfunction "A_A") (pintype "passive"))
      (node (ref "U1") (pin "11") (pinfunction "PD5(T1)_11") (pintype "bidirectional"))
    )
    (net (code "46") (name "Net-(U1-PD6(AIN0))") (class "Default")
      (node (ref "R5") (pin "A") (pinfunction "A_A") (pintype "passive"))
      (node (ref "U1") (pin "12") (pinfunction "PD6(AIN0)_12") (pintype "bidirectional"))
    )
    (net (code "47") (name "Net-(U1-PD7(AIN1))") (class "Default")
      (node (ref "R6") (pin "A") (pinfunction "A_A") (pintype "passive"))
      (node (ref "U1") (pin "13") (pinfunction "PD7(AIN1)_13") (pintype "bidirectional"))
    )
    (net (code "48") (name "unconnected-(U1-AREF-Pad21)") (class "Default")
      (node (ref "U1") (pin "21") (pinfunction "AREF_21") (pintype "bidirectional"))
    )
    (net (code "49") (name "unconnected-(U1-PD0(RXD)-Pad2)") (class "Default")
      (node (ref "U1") (pin "2") (pinfunction "PD0(RXD)_2") (pintype "bidirectional"))
    )
    (net (code "50") (name "unconnected-(U1-PD1(TXD)-Pad3)") (class "Default")
      (node (ref "U1") (pin "3") (pinfunction "PD1(TXD)_3") (pintype "bidirectional"))
    )
  )
)
